# P1.net
KiCad netlist of a schematic drawn in Altium Designer
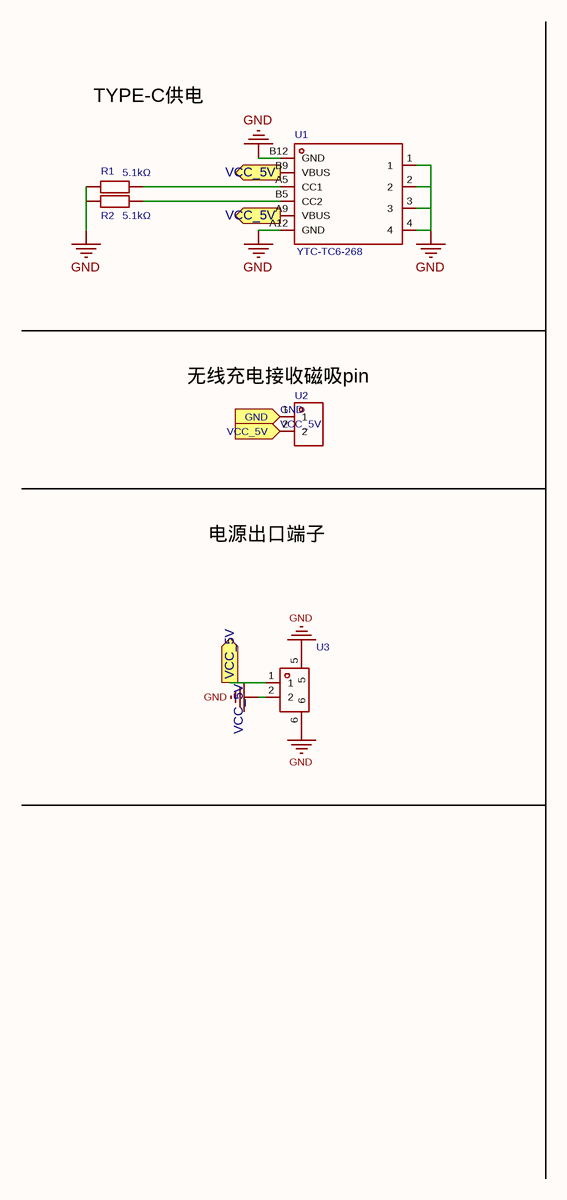
[diagram p0: P1.schdoc]

(export (version "E")
  (design (tool "Eeschema 10.0.6"))
  (components
    (comp (ref "R1")
      (value "5.1kΩ")
      (footprint "R0603_1")
      (description "电阻类型:厚膜电阻;阻值:5.1kΩ;精度:±1%;功率:100mW;温度系数:±100ppm/;最大工作电压:75V;工作温度范围:-55~+155;")
      (fields
        (field (name "MANUFACTURER") "UNI-ROYAL(厚声)")
        (field (name "MANUFACTURER PART") "0603WAF5101T5E")
      )
      (libsource (lib "altium-import") (part "root_0_0603WAF5101T5E_"))
    )
    (comp (ref "R2")
      (value "5.1kΩ")
      (footprint "R0603_1")
      (description "电阻类型:厚膜电阻;阻值:5.1kΩ;精度:±1%;功率:100mW;温度系数:±100ppm/;最大工作电压:75V;工作温度范围:-55~+155;")
      (fields
        (field (name "MANUFACTURER") "UNI-ROYAL(厚声)")
        (field (name "MANUFACTURER PART") "0603WAF5101T5E")
      )
      (libsource (lib "altium-import") (part "root_0_0603WAF5101T5E_"))
    )
    (comp (ref "U1")
      (value "YTC-TC6-268")
      (footprint "TYPE-C-SMD_YIYUAN_YTC-TC6-268")
      (description "连接器类型:Type-C;公母:母座;触点数量:6;")
      (fields (field (name "MANUFACTURER") "YIYUAN(怡远)"))
      (libsource (lib "altium-import") (part "root_0_YTC-TC6-268_"))
    )
    (comp (ref "U2")
      (value "PR5L4015-2P-C-F")
      (footprint "CONN-TH_PR5L4015-2P-C-F")
      (fields (field (name "MANUFACTURER") "SAMZO(三佐)"))
      (libsource (lib "altium-import") (part "root_0_PR5L4015-2P-C-F_"))
    )
    (comp (ref "U3")
      (value "1.0WT-2P")
      (footprint "CONN-SMD_2P-P1.00-WT")
      (libsource (lib "altium-import") (part "root_0_1.0WT-2P_"))
    )
  )
  (nets
    (net (code "1") (name "/VCC_5V") (class "Default")
      (node (ref "U1") (pin "A9") (pinfunction "VBUS_A9") (pintype "passive"))
      (node (ref "U1") (pin "B9") (pinfunction "VBUS_B9") (pintype "passive"))
      (node (ref "U2") (pin "2") (pinfunction "2_2") (pintype "passive"))
      (node (ref "U3") (pin "1") (pinfunction "1_1") (pintype "passive"))
    )
    (net (code "2") (name "GND") (class "Default")
      (node (ref "R1") (pin "1") (pinfunction "1_1") (pintype "passive"))
      (node (ref "R2") (pin "1") (pinfunction "1_1") (pintype "passive"))
      (node (ref "U1") (pin "1") (pinfunction "1_1") (pintype "passive"))
      (node (ref "U1") (pin "2") (pinfunction "2_2") (pintype "passive"))
      (node (ref "U1") (pin "3") (pinfunction "3_3") (pintype "passive"))
      (node (ref "U1") (pin "4") (pinfunction "4_4") (pintype "passive"))
      (node (ref "U1") (pin "A12") (pinfunction "GND_A12") (pintype "passive"))
      (node (ref "U1") (pin "B12") (pinfunction "GND_B12") (pintype "passive"))
      (node (ref "U2") (pin "1") (pinfunction "1_1") (pintype "passive"))
      (node (ref "U3") (pin "2") (pinfunction "2_2") (pintype "passive"))
      (node (ref "U3") (pin "5") (pinfunction "5_5") (pintype "passive"))
      (node (ref "U3") (pin "6") (pinfunction "6_6") (pintype "passive"))
    )
    (net (code "3") (name "Net-(U1-CC1)") (class "Default")
      (node (ref "R1") (pin "2") (pinfunction "2_2") (pintype "passive"))
      (node (ref "U1") (pin "A5") (pinfunction "CC1_A5") (pintype "passive"))
    )
    (net (code "4") (name "Net-(U1-CC2)") (class "Default")
      (node (ref "R2") (pin "2") (pinfunction "2_2") (pintype "passive"))
      (node (ref "U1") (pin "B5") (pinfunction "CC2_B5") (pintype "passive"))
    )
  )
)
